# M_2_M_NVMe.net
KiCad netlist of a schematic drawn in Altium Designer
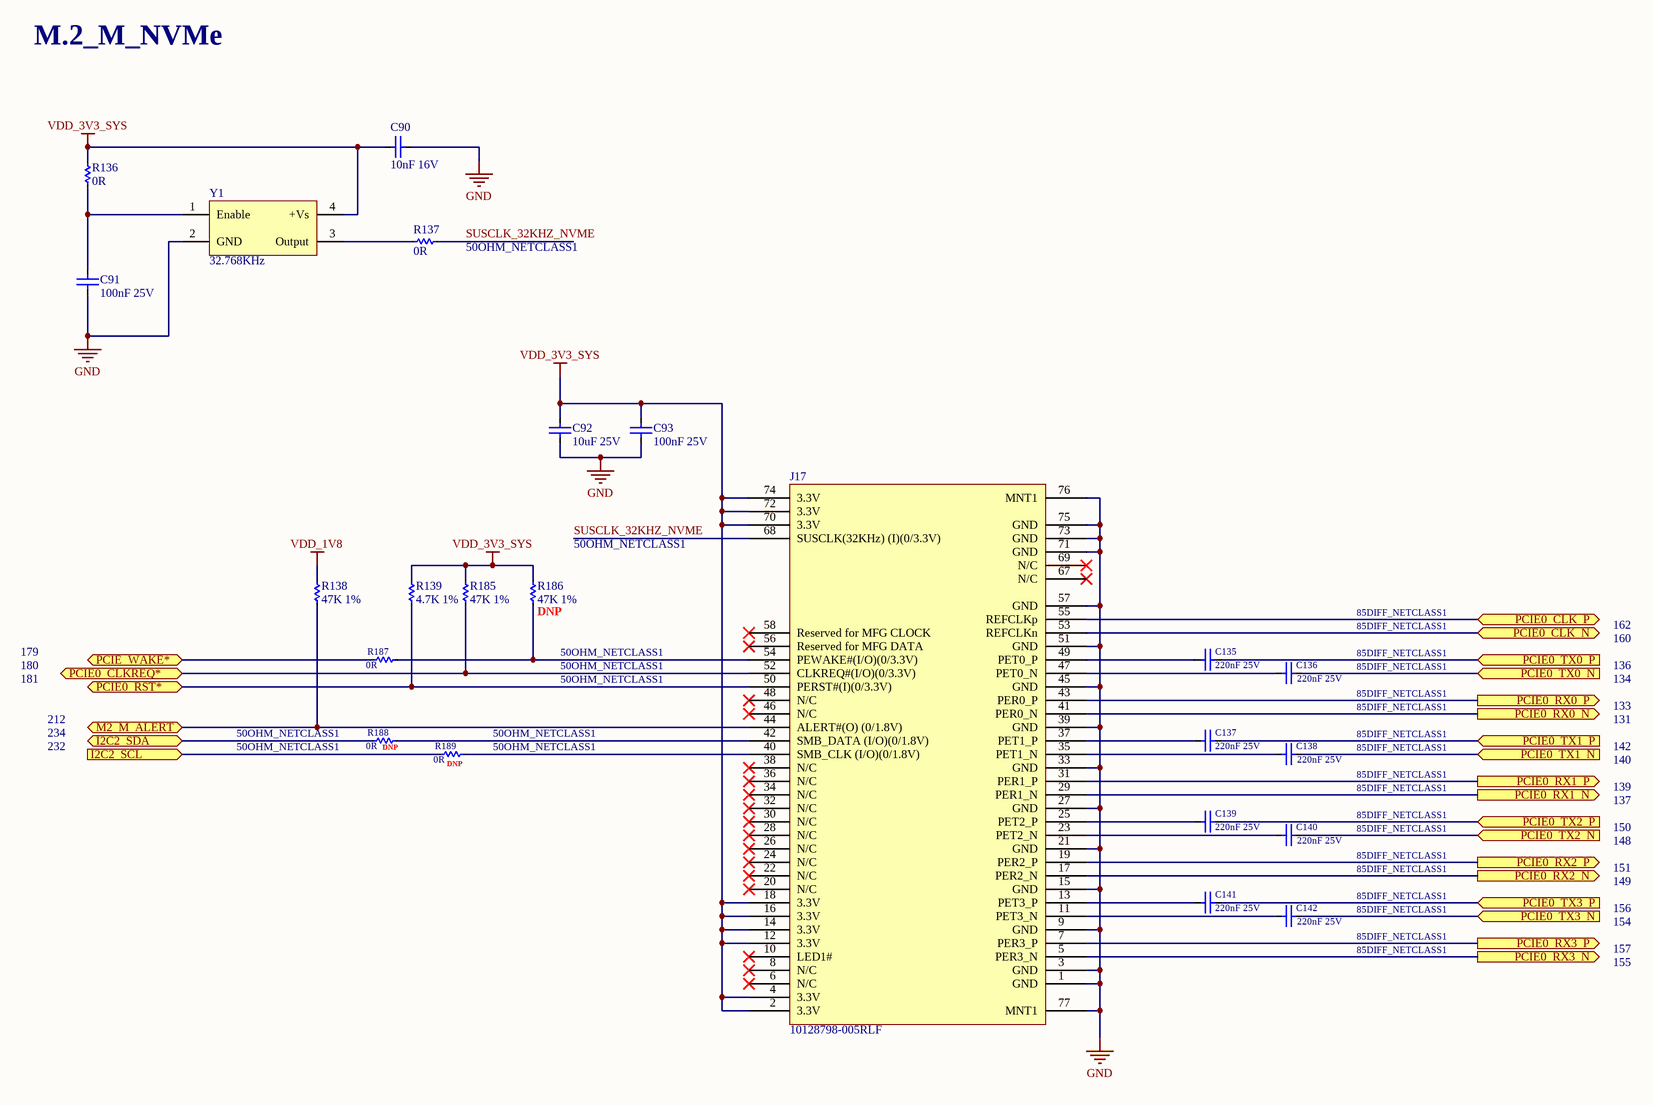
[diagram p0: M.2_M_NVMe.SchDoc]

(export (version "E")
  (design (tool "Eeschema 10.0.6"))
  (components
    (comp (ref "C90")
      (value "10nF 16V")
      (footprint "C0402")
      (description "Cap Ceramic 0.01uF 16V X7R 10% SMD 0402 125°C Paper T/R")
      (fields
        (field (name "MANUFACTURER") "Kyocera AVX")
        (field (name "MANUFACTURER PART NUMBER") "0402YC103KAT2A")
      )
      (libsource (lib "GM_Altium_Library") (part "0402YC103KAT2A"))
    )
    (comp (ref "C91")
      (value "100nF 25V")
      (footprint "C0402")
      (description "CAP CER 0.1UF 25V X5R 0402 / High Value Multilayer Ceramic Capacitors (High dielectric type)")
      (fields
        (field (name "MANUFACTURER") "Taiyo Yuden")
        (field (name "MANUFACTURER PART NUMBER") "TMK105BJ104KV-F")
      )
      (libsource (lib "GM_Altium_Library") (part "TMK105BJ104KV-F"))
    )
    (comp (ref "C92")
      (value "10uF 25V")
      (footprint "C0805")
      (description "0805 10 uF 25 V ±10% Tolerance X5R SMT Multilayer Ceramic Capacitor")
      (fields
        (field (name "MANUFACTURER") "Taiyo Yuden")
        (field (name "MANUFACTURER PART NUMBER") "TMK212BBJ106KG-T")
      )
      (libsource (lib "GM_Altium_Library") (part "TMK212BBJ106KG-T"))
    )
    (comp (ref "C93")
      (value "100nF 25V")
      (footprint "C0402")
      (description "CAP CER 0.1UF 25V X5R 0402 / High Value Multilayer Ceramic Capacitors (High dielectric type)")
      (fields
        (field (name "MANUFACTURER") "Taiyo Yuden")
        (field (name "MANUFACTURER PART NUMBER") "TMK105BJ104KV-F")
      )
      (libsource (lib "GM_Altium_Library") (part "TMK105BJ104KV-F"))
    )
    (comp (ref "C135")
      (value "220nF 25V")
      (footprint "C0402")
      (description "Cap Cer 0402 220NF 25VDC X7R")
      (fields
        (field (name "MANUFACTURER") "KEMET")
        (field (name "MANUFACTURER PART NUMBER") "C0402C224M3RAC7867")
      )
      (libsource (lib "GM_Altium_Library") (part "C0402C224M3RAC7867"))
    )
    (comp (ref "C136")
      (value "220nF 25V")
      (footprint "C0402")
      (description "Cap Cer 0402 220NF 25VDC X7R")
      (fields
        (field (name "MANUFACTURER") "KEMET")
        (field (name "MANUFACTURER PART NUMBER") "C0402C224M3RAC7867")
      )
      (libsource (lib "GM_Altium_Library") (part "C0402C224M3RAC7867"))
    )
    (comp (ref "C137")
      (value "220nF 25V")
      (footprint "C0402")
      (description "Cap Cer 0402 220NF 25VDC X7R")
      (fields
        (field (name "MANUFACTURER") "KEMET")
        (field (name "MANUFACTURER PART NUMBER") "C0402C224M3RAC7867")
      )
      (libsource (lib "GM_Altium_Library") (part "C0402C224M3RAC7867"))
    )
    (comp (ref "C138")
      (value "220nF 25V")
      (footprint "C0402")
      (description "Cap Cer 0402 220NF 25VDC X7R")
      (fields
        (field (name "MANUFACTURER") "KEMET")
        (field (name "MANUFACTURER PART NUMBER") "C0402C224M3RAC7867")
      )
      (libsource (lib "GM_Altium_Library") (part "C0402C224M3RAC7867"))
    )
    (comp (ref "C139")
      (value "220nF 25V")
      (footprint "C0402")
      (description "Cap Cer 0402 220NF 25VDC X7R")
      (fields
        (field (name "MANUFACTURER") "KEMET")
        (field (name "MANUFACTURER PART NUMBER") "C0402C224M3RAC7867")
      )
      (libsource (lib "GM_Altium_Library") (part "C0402C224M3RAC7867"))
    )
    (comp (ref "C140")
      (value "220nF 25V")
      (footprint "C0402")
      (description "Cap Cer 0402 220NF 25VDC X7R")
      (fields
        (field (name "MANUFACTURER") "KEMET")
        (field (name "MANUFACTURER PART NUMBER") "C0402C224M3RAC7867")
      )
      (libsource (lib "GM_Altium_Library") (part "C0402C224M3RAC7867"))
    )
    (comp (ref "C141")
      (value "220nF 25V")
      (footprint "C0402")
      (description "Cap Cer 0402 220NF 25VDC X7R")
      (fields
        (field (name "MANUFACTURER") "KEMET")
        (field (name "MANUFACTURER PART NUMBER") "C0402C224M3RAC7867")
      )
      (libsource (lib "GM_Altium_Library") (part "C0402C224M3RAC7867"))
    )
    (comp (ref "C142")
      (value "220nF 25V")
      (footprint "C0402")
      (description "Cap Cer 0402 220NF 25VDC X7R")
      (fields
        (field (name "MANUFACTURER") "KEMET")
        (field (name "MANUFACTURER PART NUMBER") "C0402C224M3RAC7867")
      )
      (libsource (lib "GM_Altium_Library") (part "C0402C224M3RAC7867"))
    )
    (comp (ref "J17")
      (value "10128798-005RLF")
      (footprint "10128798-005RLF")
      (description "PCIe M.2 Connectors, Storage and Server Connector, P=0.5mm, H5.5mm, Key M, 30u\" Au Plating")
      (fields (field (name "MANUFACTURER") "Amphenol Communications Solutions"))
      (libsource (lib "GM_Altium_Library") (part "10128798-005RLF"))
    )
    (comp (ref "R136")
      (value "0R")
      (footprint "R0603")
      (description "RES SMD 0 OHM JUMPER 1/10W 0603")
      (fields
        (field (name "MANUFACTURER") "Bourns")
        (field (name "MANUFACTURER PART NUMBER") "CR0603-J/-000ELF")
      )
      (libsource (lib "GM_Altium_Library") (part "CR0603-J/-000ELF"))
    )
    (comp (ref "R137")
      (value "0R")
      (footprint "R0603")
      (description "RES SMD 0 OHM JUMPER 1/10W 0603")
      (fields
        (field (name "MANUFACTURER") "Bourns")
        (field (name "MANUFACTURER PART NUMBER") "CR0603-J/-000ELF")
      )
      (libsource (lib "GM_Altium_Library") (part "CR0603-J/-000ELF"))
    )
    (comp (ref "R138")
      (value "47K 1%")
      (footprint "R0402")
      (description "Res General Purpose Thick Film 0402 47K Ohm 1% 1/16W ±100ppm/°C Molded SMD Paper T/R")
      (fields
        (field (name "MANUFACTURER") "Yageo")
        (field (name "MANUFACTURER PART NUMBER") "RC0402FR-0747KL")
      )
      (libsource (lib "GM_Altium_Library") (part "RC0402FR-0747KL"))
    )
    (comp (ref "R139")
      (value "4.7K 1%")
      (footprint "R0402")
      (description "YAGEO (PHYCOMP) - RC0402FR-074K7L - RES, THICK FILM, 4K7, 1%, 0.063W, 0402")
      (fields
        (field (name "MANUFACTURER") "Yageo")
        (field (name "MANUFACTURER PART NUMBER") "RC0402FR-074K7L")
      )
      (libsource (lib "GM_Altium_Library") (part "RC0402FR-074K7L"))
    )
    (comp (ref "R185")
      (value "47K 1%")
      (footprint "R0402")
      (description "Res General Purpose Thick Film 0402 47K Ohm 1% 1/16W ±100ppm/°C Molded SMD Paper T/R")
      (fields
        (field (name "MANUFACTURER") "Yageo")
        (field (name "MANUFACTURER PART NUMBER") "RC0402FR-0747KL")
      )
      (libsource (lib "GM_Altium_Library") (part "RC0402FR-0747KL"))
    )
    (comp (ref "R186")
      (value "47K 1%")
      (footprint "R0402")
      (description "Res General Purpose Thick Film 0402 47K Ohm 1% 1/16W ±100ppm/°C Molded SMD Paper T/R")
      (fields
        (field (name "MANUFACTURER") "Yageo")
        (field (name "MANUFACTURER PART NUMBER") "RC0402FR-0747KL")
      )
      (libsource (lib "GM_Altium_Library") (part "RC0402FR-0747KL"))
    )
    (comp (ref "R187")
      (value "0R")
      (footprint "R0603")
      (description "RES SMD 0 OHM JUMPER 1/10W 0603")
      (fields
        (field (name "MANUFACTURER") "Bourns")
        (field (name "MANUFACTURER PART NUMBER") "CR0603-J/-000ELF")
      )
      (libsource (lib "GM_Altium_Library") (part "CR0603-J/-000ELF"))
    )
    (comp (ref "R188")
      (value "0R")
      (footprint "R0603")
      (description "RES SMD 0 OHM JUMPER 1/10W 0603")
      (fields
        (field (name "MANUFACTURER") "Bourns")
        (field (name "MANUFACTURER PART NUMBER") "CR0603-J/-000ELF")
      )
      (libsource (lib "GM_Altium_Library") (part "CR0603-J/-000ELF"))
    )
    (comp (ref "R189")
      (value "0R")
      (footprint "R0603")
      (description "RES SMD 0 OHM JUMPER 1/10W 0603")
      (fields
        (field (name "MANUFACTURER") "Bourns")
        (field (name "MANUFACTURER PART NUMBER") "CR0603-J/-000ELF")
      )
      (libsource (lib "GM_Altium_Library") (part "CR0603-J/-000ELF"))
    )
    (comp (ref "Y1")
      (value "32.768KHz")
      (footprint "D2SX003270004E")
      (description "Osc 2520 32.768KHZ Cmos")
      (fields
        (field (name "MANUFACTURER") "Hosonic Electronic")
        (field (name "MANUFACTURER PART NUMBER") "D2SX003270004E")
      )
      (libsource (lib "GM_Altium_Library") (part "D2SX003270004E"))
    )
  )
  (nets
    (net (code "1") (name "/I2C2_SCL") (class "Default")
      (node (ref "R189") (pin "2") (pinfunction "2_2") (pintype "passive"))
    )
    (net (code "2") (name "/I2C2_SDA") (class "Default")
      (node (ref "R188") (pin "2") (pinfunction "2_2") (pintype "passive"))
    )
    (net (code "3") (name "/M2_M_ALERT") (class "Default")
      (node (ref "J17") (pin "44") (pinfunction "ALERT#(O)_(0/1.8V)_44") (pintype "passive"))
      (node (ref "R138") (pin "1") (pinfunction "1_1") (pintype "passive"))
    )
    (net (code "4") (name "/PCIE0_CLKREQ*") (class "Default")
      (node (ref "J17") (pin "52") (pinfunction "CLKREQ#(I/O)(0/3.3V)_52") (pintype "passive"))
      (node (ref "R185") (pin "1") (pinfunction "1_1") (pintype "passive"))
    )
    (net (code "5") (name "/PCIE0_CLK_N") (class "Default")
      (node (ref "J17") (pin "53") (pinfunction "REFCLKn_53") (pintype "passive"))
    )
    (net (code "6") (name "/PCIE0_CLK_P") (class "Default")
      (node (ref "J17") (pin "55") (pinfunction "REFCLKp_55") (pintype "passive"))
    )
    (net (code "7") (name "/PCIE0_RST*") (class "Default")
      (node (ref "J17") (pin "50") (pinfunction "PERST#(I)(0/3.3V)_50") (pintype "passive"))
      (node (ref "R139") (pin "1") (pinfunction "1_1") (pintype "passive"))
    )
    (net (code "8") (name "/PCIE0_RX0_N") (class "Default")
      (node (ref "J17") (pin "41") (pinfunction "PER0_N_41") (pintype "passive"))
    )
    (net (code "9") (name "/PCIE0_RX0_P") (class "Default")
      (node (ref "J17") (pin "43") (pinfunction "PER0_P_43") (pintype "passive"))
    )
    (net (code "10") (name "/PCIE0_RX1_N") (class "Default")
      (node (ref "J17") (pin "29") (pinfunction "PER1_N_29") (pintype "passive"))
    )
    (net (code "11") (name "/PCIE0_RX1_P") (class "Default")
      (node (ref "J17") (pin "31") (pinfunction "PER1_P_31") (pintype "passive"))
    )
    (net (code "12") (name "/PCIE0_RX2_N") (class "Default")
      (node (ref "J17") (pin "17") (pinfunction "PER2_N_17") (pintype "passive"))
    )
    (net (code "13") (name "/PCIE0_RX2_P") (class "Default")
      (node (ref "J17") (pin "19") (pinfunction "PER2_P_19") (pintype "passive"))
    )
    (net (code "14") (name "/PCIE0_RX3_N") (class "Default")
      (node (ref "J17") (pin "5") (pinfunction "PER3_N_5") (pintype "passive"))
    )
    (net (code "15") (name "/PCIE0_RX3_P") (class "Default")
      (node (ref "J17") (pin "7") (pinfunction "PER3_P_7") (pintype "passive"))
    )
    (net (code "16") (name "/PCIE0_TX0_N") (class "Default")
      (node (ref "C136") (pin "2") (pinfunction "2_2") (pintype "passive"))
    )
    (net (code "17") (name "/PCIE0_TX0_P") (class "Default")
      (node (ref "C135") (pin "2") (pinfunction "2_2") (pintype "passive"))
    )
    (net (code "18") (name "/PCIE0_TX1_N") (class "Default")
      (node (ref "C138") (pin "2") (pinfunction "2_2") (pintype "passive"))
    )
    (net (code "19") (name "/PCIE0_TX1_P") (class "Default")
      (node (ref "C137") (pin "2") (pinfunction "2_2") (pintype "passive"))
    )
    (net (code "20") (name "/PCIE0_TX2_N") (class "Default")
      (node (ref "C140") (pin "2") (pinfunction "2_2") (pintype "passive"))
    )
    (net (code "21") (name "/PCIE0_TX2_P") (class "Default")
      (node (ref "C139") (pin "2") (pinfunction "2_2") (pintype "passive"))
    )
    (net (code "22") (name "/PCIE0_TX3_N") (class "Default")
      (node (ref "C142") (pin "2") (pinfunction "2_2") (pintype "passive"))
    )
    (net (code "23") (name "/PCIE0_TX3_P") (class "Default")
      (node (ref "C141") (pin "2") (pinfunction "2_2") (pintype "passive"))
    )
    (net (code "24") (name "/PCIE_WAKE*") (class "Default")
      (node (ref "R187") (pin "2") (pinfunction "2_2") (pintype "passive"))
    )
    (net (code "25") (name "/SUSCLK_32KHZ_NVME") (class "Default")
      (node (ref "J17") (pin "68") (pinfunction "SUSCLK(32KHz)_(I)(0/3.3V)_68") (pintype "passive"))
      (node (ref "R137") (pin "1") (pinfunction "1_1") (pintype "passive"))
    )
    (net (code "26") (name "GND") (class "Default")
      (node (ref "C90") (pin "2") (pinfunction "2_2") (pintype "passive"))
      (node (ref "C91") (pin "1") (pinfunction "1_1") (pintype "passive"))
      (node (ref "C92") (pin "1") (pinfunction "1_1") (pintype "passive"))
      (node (ref "C93") (pin "1") (pinfunction "1_1") (pintype "passive"))
      (node (ref "J17") (pin "1") (pinfunction "GND_1") (pintype "passive"))
      (node (ref "J17") (pin "15") (pinfunction "GND_15") (pintype "passive"))
      (node (ref "J17") (pin "21") (pinfunction "GND_21") (pintype "passive"))
      (node (ref "J17") (pin "27") (pinfunction "GND_27") (pintype "passive"))
      (node (ref "J17") (pin "3") (pinfunction "GND_3") (pintype "passive"))
      (node (ref "J17") (pin "33") (pinfunction "GND_33") (pintype "passive"))
      (node (ref "J17") (pin "39") (pinfunction "GND_39") (pintype "passive"))
      (node (ref "J17") (pin "45") (pinfunction "GND_45") (pintype "passive"))
      (node (ref "J17") (pin "51") (pinfunction "GND_51") (pintype "passive"))
      (node (ref "J17") (pin "57") (pinfunction "GND_57") (pintype "passive"))
      (node (ref "J17") (pin "71") (pinfunction "GND_71") (pintype "passive"))
      (node (ref "J17") (pin "73") (pinfunction "GND_73") (pintype "passive"))
      (node (ref "J17") (pin "75") (pinfunction "GND_75") (pintype "passive"))
      (node (ref "J17") (pin "76") (pinfunction "MNT1_76") (pintype "passive"))
      (node (ref "J17") (pin "77") (pinfunction "MNT1_77") (pintype "passive"))
      (node (ref "J17") (pin "9") (pinfunction "GND_9") (pintype "passive"))
      (node (ref "Y1") (pin "2") (pinfunction "GND_2") (pintype "passive"))
    )
    (net (code "27") (name "Net-(J17-PET0_N)") (class "Default")
      (node (ref "C136") (pin "1") (pinfunction "1_1") (pintype "passive"))
      (node (ref "J17") (pin "47") (pinfunction "PET0_N_47") (pintype "passive"))
    )
    (net (code "28") (name "Net-(J17-PET0_P)") (class "Default")
      (node (ref "C135") (pin "1") (pinfunction "1_1") (pintype "passive"))
      (node (ref "J17") (pin "49") (pinfunction "PET0_P_49") (pintype "passive"))
    )
    (net (code "29") (name "Net-(J17-PET1_N)") (class "Default")
      (node (ref "C138") (pin "1") (pinfunction "1_1") (pintype "passive"))
      (node (ref "J17") (pin "35") (pinfunction "PET1_N_35") (pintype "passive"))
    )
    (net (code "30") (name "Net-(J17-PET1_P)") (class "Default")
      (node (ref "C137") (pin "1") (pinfunction "1_1") (pintype "passive"))
      (node (ref "J17") (pin "37") (pinfunction "PET1_P_37") (pintype "passive"))
    )
    (net (code "31") (name "Net-(J17-PET2_N)") (class "Default")
      (node (ref "C140") (pin "1") (pinfunction "1_1") (pintype "passive"))
      (node (ref "J17") (pin "23") (pinfunction "PET2_N_23") (pintype "passive"))
    )
    (net (code "32") (name "Net-(J17-PET2_P)") (class "Default")
      (node (ref "C139") (pin "1") (pinfunction "1_1") (pintype "passive"))
      (node (ref "J17") (pin "25") (pinfunction "PET2_P_25") (pintype "passive"))
    )
    (net (code "33") (name "Net-(J17-PET3_N)") (class "Default")
      (node (ref "C142") (pin "1") (pinfunction "1_1") (pintype "passive"))
      (node (ref "J17") (pin "11") (pinfunction "PET3_N_11") (pintype "passive"))
    )
    (net (code "34") (name "Net-(J17-PET3_P)") (class "Default")
      (node (ref "C141") (pin "1") (pinfunction "1_1") (pintype "passive"))
      (node (ref "J17") (pin "13") (pinfunction "PET3_P_13") (pintype "passive"))
    )
    (net (code "35") (name "Net-(J17-PEWAKE#(I{slash}O)(0{slash}3.3V))") (class "Default")
      (node (ref "J17") (pin "54") (pinfunction "PEWAKE#(I/O)(0/3.3V)_54") (pintype "passive"))
      (node (ref "R186") (pin "1") (pinfunction "1_1") (pintype "passive"))
      (node (ref "R187") (pin "1") (pinfunction "1_1") (pintype "passive"))
    )
    (net (code "36") (name "Net-(J17-SMB_CLK_(I{slash}O)(0{slash}1.8V))") (class "Default")
      (node (ref "J17") (pin "40") (pinfunction "SMB_CLK_(I/O)(0/1.8V)_40") (pintype "passive"))
      (node (ref "R189") (pin "1") (pinfunction "1_1") (pintype "passive"))
    )
    (net (code "37") (name "Net-(J17-SMB_DATA_(I{slash}O)(0{slash}1.8V))") (class "Default")
      (node (ref "J17") (pin "42") (pinfunction "SMB_DATA_(I/O)(0/1.8V)_42") (pintype "passive"))
      (node (ref "R188") (pin "1") (pinfunction "1_1") (pintype "passive"))
    )
    (net (code "38") (name "Net-(Y1-Enable)") (class "Default")
      (node (ref "C91") (pin "2") (pinfunction "2_2") (pintype "passive"))
      (node (ref "R136") (pin "1") (pinfunction "1_1") (pintype "passive"))
      (node (ref "Y1") (pin "1") (pinfunction "Enable_1") (pintype "passive"))
    )
    (net (code "39") (name "Net-(Y1-Output)") (class "Default")
      (node (ref "R137") (pin "2") (pinfunction "2_2") (pintype "passive"))
      (node (ref "Y1") (pin "3") (pinfunction "Output_3") (pintype "passive"))
    )
    (net (code "40") (name "VDD_1V8") (class "Default")
      (node (ref "R138") (pin "2") (pinfunction "2_2") (pintype "passive"))
    )
    (net (code "41") (name "VDD_3V3_SYS") (class "Default")
      (node (ref "C90") (pin "1") (pinfunction "1_1") (pintype "passive"))
      (node (ref "C92") (pin "2") (pinfunction "2_2") (pintype "passive"))
      (node (ref "C93") (pin "2") (pinfunction "2_2") (pintype "passive"))
      (node (ref "J17") (pin "12") (pinfunction "3.3V_12") (pintype "passive"))
      (node (ref "J17") (pin "14") (pinfunction "3.3V_14") (pintype "passive"))
      (node (ref "J17") (pin "16") (pinfunction "3.3V_16") (pintype "passive"))
      (node (ref "J17") (pin "18") (pinfunction "3.3V_18") (pintype "passive"))
      (node (ref "J17") (pin "2") (pinfunction "3.3V_2") (pintype "passive"))
      (node (ref "J17") (pin "4") (pinfunction "3.3V_4") (pintype "passive"))
      (node (ref "J17") (pin "70") (pinfunction "3.3V_70") (pintype "passive"))
      (node (ref "J17") (pin "72") (pinfunction "3.3V_72") (pintype "passive"))
      (node (ref "J17") (pin "74") (pinfunction "3.3V_74") (pintype "passive"))
      (node (ref "R136") (pin "2") (pinfunction "2_2") (pintype "passive"))
      (node (ref "R139") (pin "2") (pinfunction "2_2") (pintype "passive"))
      (node (ref "R185") (pin "2") (pinfunction "2_2") (pintype "passive"))
      (node (ref "R186") (pin "2") (pinfunction "2_2") (pintype "passive"))
      (node (ref "Y1") (pin "4") (pinfunction "+Vs_4") (pintype "passive"))
    )
    (net (code "42") (name "unconnected-(J17-LED1#-Pad10)") (class "Default")
      (node (ref "J17") (pin "10") (pinfunction "LED1#_10") (pintype "passive+no_connect"))
    )
    (net (code "43") (name "unconnected-(J17-N{slash}C-Pad6)") (class "Default")
      (node (ref "J17") (pin "6") (pinfunction "N/C_6") (pintype "passive+no_connect"))
    )
    (net (code "44") (name "unconnected-(J17-N{slash}C-Pad8)") (class "Default")
      (node (ref "J17") (pin "8") (pinfunction "N/C_8") (pintype "passive+no_connect"))
    )
    (net (code "45") (name "unconnected-(J17-N{slash}C-Pad20)") (class "Default")
      (node (ref "J17") (pin "20") (pinfunction "N/C_20") (pintype "passive+no_connect"))
    )
    (net (code "46") (name "unconnected-(J17-N{slash}C-Pad22)") (class "Default")
      (node (ref "J17") (pin "22") (pinfunction "N/C_22") (pintype "passive+no_connect"))
    )
    (net (code "47") (name "unconnected-(J17-N{slash}C-Pad24)") (class "Default")
      (node (ref "J17") (pin "24") (pinfunction "N/C_24") (pintype "passive+no_connect"))
    )
    (net (code "48") (name "unconnected-(J17-N{slash}C-Pad26)") (class "Default")
      (node (ref "J17") (pin "26") (pinfunction "N/C_26") (pintype "passive+no_connect"))
    )
    (net (code "49") (name "unconnected-(J17-N{slash}C-Pad28)") (class "Default")
      (node (ref "J17") (pin "28") (pinfunction "N/C_28") (pintype "passive+no_connect"))
    )
    (net (code "50") (name "unconnected-(J17-N{slash}C-Pad30)") (class "Default")
      (node (ref "J17") (pin "30") (pinfunction "N/C_30") (pintype "passive+no_connect"))
    )
    (net (code "51") (name "unconnected-(J17-N{slash}C-Pad32)") (class "Default")
      (node (ref "J17") (pin "32") (pinfunction "N/C_32") (pintype "passive+no_connect"))
    )
    (net (code "52") (name "unconnected-(J17-N{slash}C-Pad34)") (class "Default")
      (node (ref "J17") (pin "34") (pinfunction "N/C_34") (pintype "passive+no_connect"))
    )
    (net (code "53") (name "unconnected-(J17-N{slash}C-Pad36)") (class "Default")
      (node (ref "J17") (pin "36") (pinfunction "N/C_36") (pintype "passive+no_connect"))
    )
    (net (code "54") (name "unconnected-(J17-N{slash}C-Pad38)") (class "Default")
      (node (ref "J17") (pin "38") (pinfunction "N/C_38") (pintype "passive+no_connect"))
    )
    (net (code "55") (name "unconnected-(J17-N{slash}C-Pad46)") (class "Default")
      (node (ref "J17") (pin "46") (pinfunction "N/C_46") (pintype "passive+no_connect"))
    )
    (net (code "56") (name "unconnected-(J17-N{slash}C-Pad48)") (class "Default")
      (node (ref "J17") (pin "48") (pinfunction "N/C_48") (pintype "passive+no_connect"))
    )
    (net (code "57") (name "unconnected-(J17-N{slash}C-Pad67)") (class "Default")
      (node (ref "J17") (pin "67") (pinfunction "N/C_67") (pintype "passive+no_connect"))
    )
    (net (code "58") (name "unconnected-(J17-N{slash}C-Pad69)") (class "Default")
      (node (ref "J17") (pin "69") (pinfunction "N/C_69") (pintype "passive+no_connect"))
    )
    (net (code "59") (name "unconnected-(J17-Reserved_for_MFG_CLOCK-Pad58)") (class "Default")
      (node (ref "J17") (pin "58") (pinfunction "Reserved_for_MFG_CLOCK_58") (pintype "passive+no_connect"))
    )
    (net (code "60") (name "unconnected-(J17-Reserved_for_MFG_DATA-Pad56)") (class "Default")
      (node (ref "J17") (pin "56") (pinfunction "Reserved_for_MFG_DATA_56") (pintype "passive+no_connect"))
    )
  )
)
